# CLKB_clocking_system.net
KiCad netlist of a schematic drawn in Altium Designer
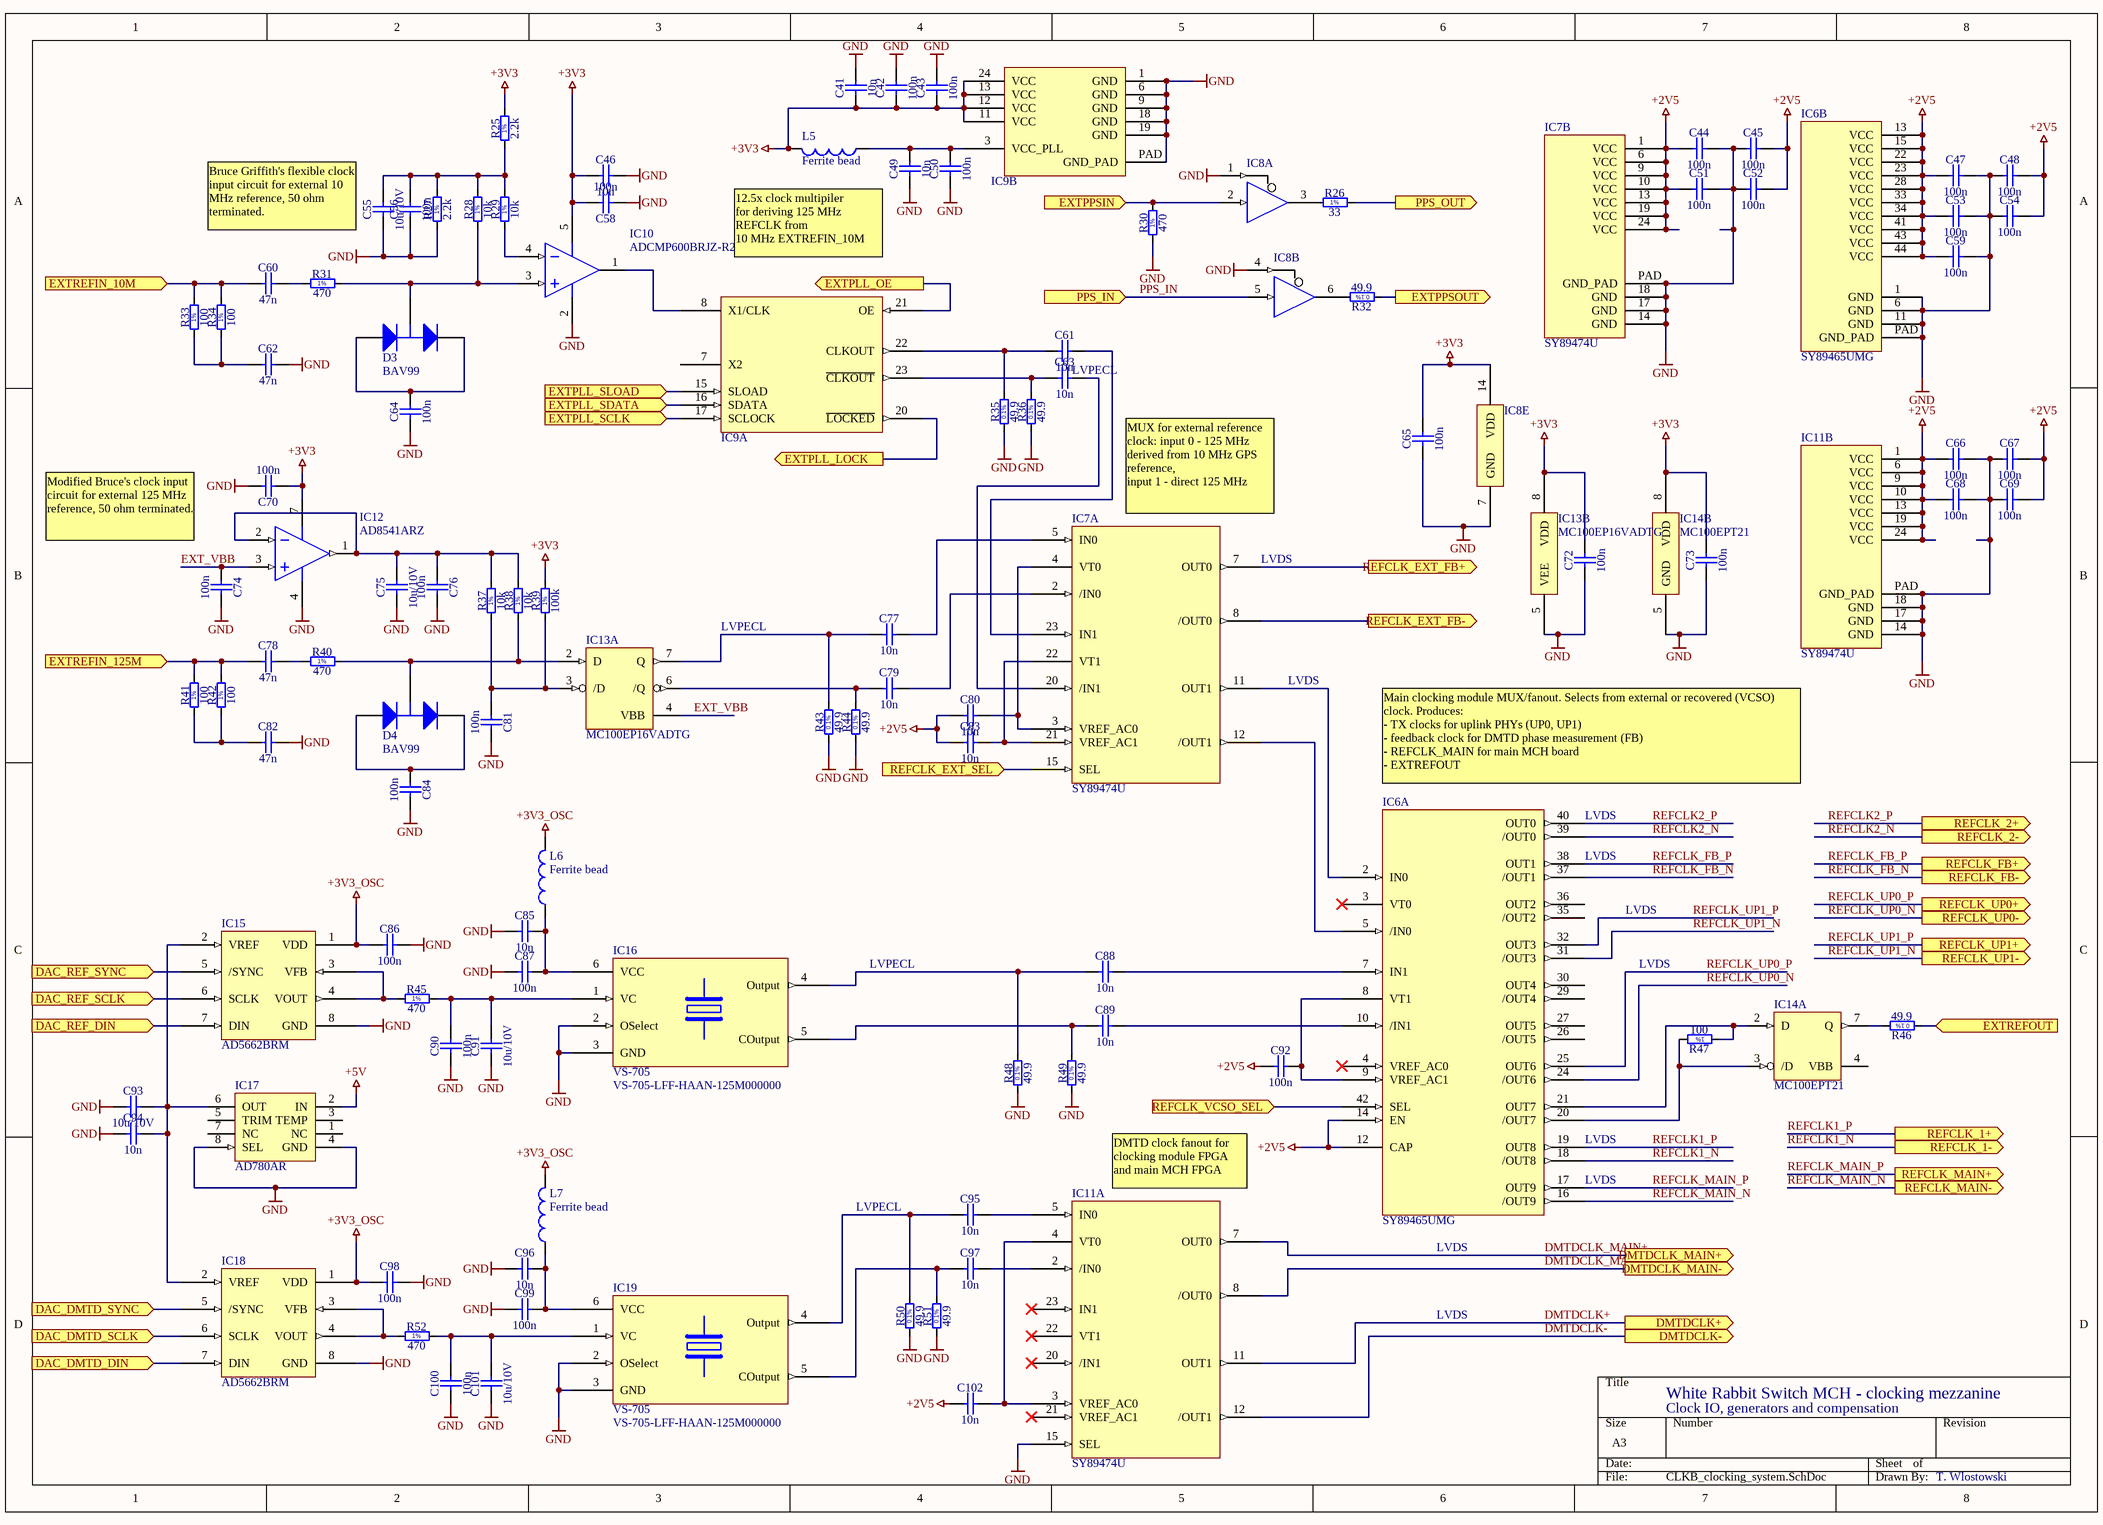
[diagram p0: CLKB_clocking_system.SchDoc]

(export (version "E")
  (design (tool "Eeschema 10.0.6"))
  (components
    (comp (ref "C41")
      (value "10n")
      (footprint "CAPC1608X87N")
      (description "Non-polarised capacitor")
      (fields
        (field (name "PART NUMBER") "CC0603_10NF_50V_10%_X7R")
        (field (name "VOLTAGE") "50V")
        (field (name "AUTHOR") "CERN DEM JLC")
      )
      (libsource (lib "Capacitors") (part "Capacitor - non polarized"))
    )
    (comp (ref "C42")
      (value "100n")
      (footprint "CAPC1608X87N")
      (description "Non-polarised capacitor")
      (fields
        (field (name "PART NUMBER") "CC0603_100NF_50V_10%_X7R")
        (field (name "VOLTAGE") "50V")
        (field (name "AUTHOR") "CERN DEM JLC")
      )
      (libsource (lib "Capacitors") (part "Capacitor - non polarized"))
    )
    (comp (ref "C43")
      (value "100n")
      (footprint "CAPC1608X87N")
      (description "Non-polarised capacitor")
      (fields
        (field (name "PART NUMBER") "CC0603_100NF_50V_10%_X7R")
        (field (name "VOLTAGE") "50V")
        (field (name "AUTHOR") "CERN DEM JLC")
      )
      (libsource (lib "Capacitors") (part "Capacitor - non polarized"))
    )
    (comp (ref "C44")
      (value "100n")
      (footprint "CAPC1608X87N")
      (description "Non-polarised capacitor")
      (fields
        (field (name "PART NUMBER") "CC0603_100NF_50V_10%_X7R")
        (field (name "VOLTAGE") "50V")
        (field (name "AUTHOR") "CERN DEM JLC")
      )
      (libsource (lib "Capacitors") (part "Capacitor - non polarized"))
    )
    (comp (ref "C45")
      (value "100n")
      (footprint "CAPC1608X87N")
      (description "Non-polarised capacitor")
      (fields
        (field (name "PART NUMBER") "CC0603_100NF_50V_10%_X7R")
        (field (name "VOLTAGE") "50V")
        (field (name "AUTHOR") "CERN DEM JLC")
      )
      (libsource (lib "Capacitors") (part "Capacitor - non polarized"))
    )
    (comp (ref "C46")
      (value "10n")
      (footprint "CAPC1608X87N")
      (description "Non-polarised capacitor")
      (fields
        (field (name "PART NUMBER") "CC0603_10NF_50V_10%_X7R")
        (field (name "VOLTAGE") "50V")
        (field (name "AUTHOR") "CERN DEM JLC")
      )
      (libsource (lib "Capacitors") (part "Capacitor - non polarized"))
    )
    (comp (ref "C47")
      (value "100n")
      (footprint "CAPC1608X87N")
      (description "Non-polarised capacitor")
      (fields
        (field (name "PART NUMBER") "CC0603_100NF_50V_10%_X7R")
        (field (name "VOLTAGE") "50V")
        (field (name "AUTHOR") "CERN DEM JLC")
      )
      (libsource (lib "Capacitors") (part "Capacitor - non polarized"))
    )
    (comp (ref "C48")
      (value "100n")
      (footprint "CAPC1608X87N")
      (description "Non-polarised capacitor")
      (fields
        (field (name "PART NUMBER") "CC0603_100NF_50V_10%_X7R")
        (field (name "VOLTAGE") "50V")
        (field (name "AUTHOR") "CERN DEM JLC")
      )
      (libsource (lib "Capacitors") (part "Capacitor - non polarized"))
    )
    (comp (ref "C49")
      (value "10n")
      (footprint "CAPC1608X87N")
      (description "Non-polarised capacitor")
      (fields
        (field (name "PART NUMBER") "CC0603_10NF_50V_10%_X7R")
        (field (name "VOLTAGE") "50V")
        (field (name "AUTHOR") "CERN DEM JLC")
      )
      (libsource (lib "Capacitors") (part "Capacitor - non polarized"))
    )
    (comp (ref "C50")
      (value "100n")
      (footprint "CAPC1608X87N")
      (description "Non-polarised capacitor")
      (fields
        (field (name "PART NUMBER") "CC0603_100NF_50V_10%_X7R")
        (field (name "VOLTAGE") "50V")
        (field (name "AUTHOR") "CERN DEM JLC")
      )
      (libsource (lib "Capacitors") (part "Capacitor - non polarized"))
    )
    (comp (ref "C51")
      (value "100n")
      (footprint "CAPC1608X87N")
      (description "Non-polarised capacitor")
      (fields
        (field (name "PART NUMBER") "CC0603_100NF_50V_10%_X7R")
        (field (name "VOLTAGE") "50V")
        (field (name "AUTHOR") "CERN DEM JLC")
      )
      (libsource (lib "Capacitors") (part "Capacitor - non polarized"))
    )
    (comp (ref "C52")
      (value "100n")
      (footprint "CAPC1608X87N")
      (description "Non-polarised capacitor")
      (fields
        (field (name "PART NUMBER") "CC0603_100NF_50V_10%_X7R")
        (field (name "VOLTAGE") "50V")
        (field (name "AUTHOR") "CERN DEM JLC")
      )
      (libsource (lib "Capacitors") (part "Capacitor - non polarized"))
    )
    (comp (ref "C53")
      (value "100n")
      (footprint "CAPC1608X87N")
      (description "Non-polarised capacitor")
      (fields
        (field (name "PART NUMBER") "CC0603_100NF_50V_10%_X7R")
        (field (name "VOLTAGE") "50V")
        (field (name "AUTHOR") "CERN DEM JLC")
      )
      (libsource (lib "Capacitors") (part "Capacitor - non polarized"))
    )
    (comp (ref "C54")
      (value "100n")
      (footprint "CAPC1608X87N")
      (description "Non-polarised capacitor")
      (fields
        (field (name "PART NUMBER") "CC0603_100NF_50V_10%_X7R")
        (field (name "VOLTAGE") "50V")
        (field (name "AUTHOR") "CERN DEM JLC")
      )
      (libsource (lib "Capacitors") (part "Capacitor - non polarized"))
    )
    (comp (ref "C55")
      (value "10u/10V")
      (footprint "CAPC3216X140N")
      (description "Non-polarised capacitor")
      (fields
        (field (name "PART NUMBER") "CC1206_10UF_10V_10%_X7R")
        (field (name "VOLTAGE") "10V")
        (field (name "AUTHOR") "CERN DEM JLC")
      )
      (libsource (lib "Capacitors") (part "Capacitor - non polarized"))
    )
    (comp (ref "C56")
      (value "100n")
      (footprint "CAPC1608X87N")
      (description "Non-polarised capacitor")
      (fields
        (field (name "PART NUMBER") "CC0603_100NF_50V_10%_X7R")
        (field (name "VOLTAGE") "50V")
        (field (name "AUTHOR") "CERN DEM JLC")
      )
      (libsource (lib "Capacitors") (part "Capacitor - non polarized"))
    )
    (comp (ref "C58")
      (value "100n")
      (footprint "CAPC1608X87N")
      (description "Non-polarised capacitor")
      (fields
        (field (name "PART NUMBER") "CC0603_100NF_50V_10%_X7R")
        (field (name "VOLTAGE") "50V")
        (field (name "AUTHOR") "CERN DEM JLC")
      )
      (libsource (lib "Capacitors") (part "Capacitor - non polarized"))
    )
    (comp (ref "C59")
      (value "100n")
      (footprint "CAPC1608X87N")
      (description "Non-polarised capacitor")
      (fields
        (field (name "PART NUMBER") "CC0603_100NF_50V_10%_X7R")
        (field (name "VOLTAGE") "50V")
        (field (name "AUTHOR") "CERN DEM JLC")
      )
      (libsource (lib "Capacitors") (part "Capacitor - non polarized"))
    )
    (comp (ref "C60")
      (value "47n")
      (footprint "CAPC1608X87N")
      (description "Non-polarised capacitor")
      (fields
        (field (name "PART NUMBER") "CC0603_47NF_25V_10%_X7R")
        (field (name "VOLTAGE") "25V")
        (field (name "AUTHOR") "CERN DEM JLC")
      )
      (libsource (lib "Capacitors") (part "Capacitor - non polarized"))
    )
    (comp (ref "C61")
      (value "10n")
      (footprint "CAPC1608X87N")
      (description "Non-polarised capacitor")
      (fields
        (field (name "PART NUMBER") "CC0603_10NF_50V_10%_X7R")
        (field (name "VOLTAGE") "50V")
        (field (name "AUTHOR") "CERN DEM JLC")
      )
      (libsource (lib "Capacitors") (part "Capacitor - non polarized"))
    )
    (comp (ref "C62")
      (value "47n")
      (footprint "CAPC1608X87N")
      (description "Non-polarised capacitor")
      (fields
        (field (name "PART NUMBER") "CC0603_47NF_25V_10%_X7R")
        (field (name "VOLTAGE") "25V")
        (field (name "AUTHOR") "CERN DEM JLC")
      )
      (libsource (lib "Capacitors") (part "Capacitor - non polarized"))
    )
    (comp (ref "C63")
      (value "10n")
      (footprint "CAPC1608X87N")
      (description "Non-polarised capacitor")
      (fields
        (field (name "PART NUMBER") "CC0603_10NF_50V_10%_X7R")
        (field (name "VOLTAGE") "50V")
        (field (name "AUTHOR") "CERN DEM JLC")
      )
      (libsource (lib "Capacitors") (part "Capacitor - non polarized"))
    )
    (comp (ref "C64")
      (value "100n")
      (footprint "CAPC1608X87N")
      (description "Non-polarised capacitor")
      (fields
        (field (name "PART NUMBER") "CC0603_100NF_50V_10%_X7R")
        (field (name "VOLTAGE") "50V")
        (field (name "AUTHOR") "CERN DEM JLC")
      )
      (libsource (lib "Capacitors") (part "Capacitor - non polarized"))
    )
    (comp (ref "C65")
      (value "100n")
      (footprint "CAPC1608X87N")
      (description "Non-polarised capacitor")
      (fields
        (field (name "PART NUMBER") "CC0603_100NF_50V_10%_X7R")
        (field (name "VOLTAGE") "50V")
        (field (name "AUTHOR") "CERN DEM JLC")
      )
      (libsource (lib "Capacitors") (part "Capacitor - non polarized"))
    )
    (comp (ref "C66")
      (value "100n")
      (footprint "CAPC1608X87N")
      (description "Non-polarised capacitor")
      (fields
        (field (name "PART NUMBER") "CC0603_100NF_50V_10%_X7R")
        (field (name "VOLTAGE") "50V")
        (field (name "AUTHOR") "CERN DEM JLC")
      )
      (libsource (lib "Capacitors") (part "Capacitor - non polarized"))
    )
    (comp (ref "C67")
      (value "100n")
      (footprint "CAPC1608X87N")
      (description "Non-polarised capacitor")
      (fields
        (field (name "PART NUMBER") "CC0603_100NF_50V_10%_X7R")
        (field (name "VOLTAGE") "50V")
        (field (name "AUTHOR") "CERN DEM JLC")
      )
      (libsource (lib "Capacitors") (part "Capacitor - non polarized"))
    )
    (comp (ref "C68")
      (value "100n")
      (footprint "CAPC1608X87N")
      (description "Non-polarised capacitor")
      (fields
        (field (name "PART NUMBER") "CC0603_100NF_50V_10%_X7R")
        (field (name "VOLTAGE") "50V")
        (field (name "AUTHOR") "CERN DEM JLC")
      )
      (libsource (lib "Capacitors") (part "Capacitor - non polarized"))
    )
    (comp (ref "C69")
      (value "100n")
      (footprint "CAPC1608X87N")
      (description "Non-polarised capacitor")
      (fields
        (field (name "PART NUMBER") "CC0603_100NF_50V_10%_X7R")
        (field (name "VOLTAGE") "50V")
        (field (name "AUTHOR") "CERN DEM JLC")
      )
      (libsource (lib "Capacitors") (part "Capacitor - non polarized"))
    )
    (comp (ref "C70")
      (value "100n")
      (footprint "CAPC1608X87N")
      (description "Non-polarised capacitor")
      (fields
        (field (name "PART NUMBER") "CC0603_100NF_50V_10%_X7R")
        (field (name "VOLTAGE") "50V")
        (field (name "AUTHOR") "CERN DEM JLC")
      )
      (libsource (lib "Capacitors") (part "Capacitor - non polarized"))
    )
    (comp (ref "C72")
      (value "100n")
      (footprint "CAPC1608X87N")
      (description "Non-polarised capacitor")
      (fields
        (field (name "PART NUMBER") "CC0603_100NF_50V_10%_X7R")
        (field (name "VOLTAGE") "50V")
        (field (name "AUTHOR") "CERN DEM JLC")
      )
      (libsource (lib "Capacitors") (part "Capacitor - non polarized"))
    )
    (comp (ref "C73")
      (value "100n")
      (footprint "CAPC1608X87N")
      (description "Non-polarised capacitor")
      (fields
        (field (name "PART NUMBER") "CC0603_100NF_50V_10%_X7R")
        (field (name "VOLTAGE") "50V")
        (field (name "AUTHOR") "CERN DEM JLC")
      )
      (libsource (lib "Capacitors") (part "Capacitor - non polarized"))
    )
    (comp (ref "C74")
      (value "100n")
      (footprint "CAPC1608X87N")
      (description "Non-polarised capacitor")
      (fields
        (field (name "PART NUMBER") "CC0603_100NF_50V_10%_X7R")
        (field (name "VOLTAGE") "50V")
        (field (name "AUTHOR") "CERN DEM JLC")
      )
      (libsource (lib "Capacitors") (part "Capacitor - non polarized"))
    )
    (comp (ref "C75")
      (value "10u/10V")
      (footprint "CAPC3216X140N")
      (description "Non-polarised capacitor")
      (fields
        (field (name "PART NUMBER") "CC1206_10UF_10V_10%_X7R")
        (field (name "VOLTAGE") "10V")
        (field (name "AUTHOR") "CERN DEM JLC")
      )
      (libsource (lib "Capacitors") (part "Capacitor - non polarized"))
    )
    (comp (ref "C76")
      (value "100n")
      (footprint "CAPC1608X87N")
      (description "Non-polarised capacitor")
      (fields
        (field (name "PART NUMBER") "CC0603_100NF_50V_10%_X7R")
        (field (name "VOLTAGE") "50V")
        (field (name "AUTHOR") "CERN DEM JLC")
      )
      (libsource (lib "Capacitors") (part "Capacitor - non polarized"))
    )
    (comp (ref "C77")
      (value "10n")
      (footprint "CAPC1608X87N")
      (description "Non-polarised capacitor")
      (fields
        (field (name "PART NUMBER") "CC0603_10NF_50V_10%_X7R")
        (field (name "VOLTAGE") "50V")
        (field (name "AUTHOR") "CERN DEM JLC")
      )
      (libsource (lib "Capacitors") (part "Capacitor - non polarized"))
    )
    (comp (ref "C78")
      (value "47n")
      (footprint "CAPC1608X87N")
      (description "Non-polarised capacitor")
      (fields
        (field (name "PART NUMBER") "CC0603_47NF_25V_10%_X7R")
        (field (name "VOLTAGE") "25V")
        (field (name "AUTHOR") "CERN DEM JLC")
      )
      (libsource (lib "Capacitors") (part "Capacitor - non polarized"))
    )
    (comp (ref "C79")
      (value "10n")
      (footprint "CAPC1608X87N")
      (description "Non-polarised capacitor")
      (fields
        (field (name "PART NUMBER") "CC0603_10NF_50V_10%_X7R")
        (field (name "VOLTAGE") "50V")
        (field (name "AUTHOR") "CERN DEM JLC")
      )
      (libsource (lib "Capacitors") (part "Capacitor - non polarized"))
    )
    (comp (ref "C80")
      (value "10n")
      (footprint "CAPC1608X87N")
      (description "Non-polarised capacitor")
      (fields
        (field (name "PART NUMBER") "CC0603_10NF_50V_10%_X7R")
        (field (name "VOLTAGE") "50V")
        (field (name "AUTHOR") "CERN DEM JLC")
      )
      (libsource (lib "Capacitors") (part "Capacitor - non polarized"))
    )
    (comp (ref "C81")
      (value "100n")
      (footprint "CAPC1608X87N")
      (description "Non-polarised capacitor")
      (fields
        (field (name "PART NUMBER") "CC0603_100NF_50V_10%_X7R")
        (field (name "VOLTAGE") "50V")
        (field (name "AUTHOR") "CERN DEM JLC")
      )
      (libsource (lib "Capacitors") (part "Capacitor - non polarized"))
    )
    (comp (ref "C82")
      (value "47n")
      (footprint "CAPC1608X87N")
      (description "Non-polarised capacitor")
      (fields
        (field (name "PART NUMBER") "CC0603_47NF_25V_10%_X7R")
        (field (name "VOLTAGE") "25V")
        (field (name "AUTHOR") "CERN DEM JLC")
      )
      (libsource (lib "Capacitors") (part "Capacitor - non polarized"))
    )
    (comp (ref "C83")
      (value "10n")
      (footprint "CAPC1608X87N")
      (description "Non-polarised capacitor")
      (fields
        (field (name "PART NUMBER") "CC0603_10NF_50V_10%_X7R")
        (field (name "VOLTAGE") "50V")
        (field (name "AUTHOR") "CERN DEM JLC")
      )
      (libsource (lib "Capacitors") (part "Capacitor - non polarized"))
    )
    (comp (ref "C84")
      (value "100n")
      (footprint "CAPC1608X87N")
      (description "Non-polarised capacitor")
      (fields
        (field (name "PART NUMBER") "CC0603_100NF_50V_10%_X7R")
        (field (name "VOLTAGE") "50V")
        (field (name "AUTHOR") "CERN DEM JLC")
      )
      (libsource (lib "Capacitors") (part "Capacitor - non polarized"))
    )
    (comp (ref "C85")
      (value "10n")
      (footprint "CAPC1608X87N")
      (description "Non-polarised capacitor")
      (fields
        (field (name "PART NUMBER") "CC0603_10NF_50V_10%_X7R")
        (field (name "VOLTAGE") "50V")
        (field (name "AUTHOR") "CERN DEM JLC")
      )
      (libsource (lib "Capacitors") (part "Capacitor - non polarized"))
    )
    (comp (ref "C86")
      (value "100n")
      (footprint "CAPC1608X87N")
      (description "Non-polarised capacitor")
      (fields
        (field (name "PART NUMBER") "CC0603_100NF_50V_10%_X7R")
        (field (name "VOLTAGE") "50V")
        (field (name "AUTHOR") "CERN DEM JLC")
      )
      (libsource (lib "Capacitors") (part "Capacitor - non polarized"))
    )
    (comp (ref "C87")
      (value "100n")
      (footprint "CAPC1608X87N")
      (description "Non-polarised capacitor")
      (fields
        (field (name "PART NUMBER") "CC0603_100NF_50V_10%_X7R")
        (field (name "VOLTAGE") "50V")
        (field (name "AUTHOR") "CERN DEM JLC")
      )
      (libsource (lib "Capacitors") (part "Capacitor - non polarized"))
    )
    (comp (ref "C88")
      (value "10n")
      (footprint "CAPC1608X87N")
      (description "Non-polarised capacitor")
      (fields
        (field (name "PART NUMBER") "CC0603_10NF_50V_10%_X7R")
        (field (name "VOLTAGE") "50V")
        (field (name "AUTHOR") "CERN DEM JLC")
      )
      (libsource (lib "Capacitors") (part "Capacitor - non polarized"))
    )
    (comp (ref "C89")
      (value "10n")
      (footprint "CAPC1608X87N")
      (description "Non-polarised capacitor")
      (fields
        (field (name "PART NUMBER") "CC0603_10NF_50V_10%_X7R")
        (field (name "VOLTAGE") "50V")
        (field (name "AUTHOR") "CERN DEM JLC")
      )
      (libsource (lib "Capacitors") (part "Capacitor - non polarized"))
    )
    (comp (ref "C90")
      (value "100n")
      (footprint "CAPC1608X87N")
      (description "Non-polarised capacitor")
      (fields
        (field (name "PART NUMBER") "CC0603_100NF_50V_10%_X7R")
        (field (name "VOLTAGE") "50V")
        (field (name "AUTHOR") "CERN DEM JLC")
      )
      (libsource (lib "Capacitors") (part "Capacitor - non polarized"))
    )
    (comp (ref "C91")
      (value "10u/10V")
      (footprint "CAPC3216X140N")
      (description "Non-polarised capacitor")
      (fields
        (field (name "PART NUMBER") "CC1206_10UF_10V_10%_X7R")
        (field (name "VOLTAGE") "10V")
        (field (name "AUTHOR") "CERN DEM JLC")
      )
      (libsource (lib "Capacitors") (part "Capacitor - non polarized"))
    )
    (comp (ref "C92")
      (value "100n")
      (footprint "CAPC1608X87N")
      (description "Non-polarised capacitor")
      (fields
        (field (name "PART NUMBER") "CC0603_100NF_50V_10%_X7R")
        (field (name "VOLTAGE") "50V")
        (field (name "AUTHOR") "CERN DEM JLC")
      )
      (libsource (lib "Capacitors") (part "Capacitor - non polarized"))
    )
    (comp (ref "C93")
      (value "10u/10V")
      (footprint "CAPC3216X140N")
      (description "Non-polarised capacitor")
      (fields
        (field (name "PART NUMBER") "CC1206_10UF_10V_10%_X7R")
        (field (name "VOLTAGE") "10V")
        (field (name "AUTHOR") "CERN DEM JLC")
      )
      (libsource (lib "Capacitors") (part "Capacitor - non polarized"))
    )
    (comp (ref "C94")
      (value "10n")
      (footprint "CAPC1608X87N")
      (description "Non-polarised capacitor")
      (fields
        (field (name "PART NUMBER") "CC0603_10NF_50V_10%_X7R")
        (field (name "VOLTAGE") "50V")
        (field (name "AUTHOR") "CERN DEM JLC")
      )
      (libsource (lib "Capacitors") (part "Capacitor - non polarized"))
    )
    (comp (ref "C95")
      (value "10n")
      (footprint "CAPC1608X87N")
      (description "Non-polarised capacitor")
      (fields
        (field (name "PART NUMBER") "CC0603_10NF_50V_10%_X7R")
        (field (name "VOLTAGE") "50V")
        (field (name "AUTHOR") "CERN DEM JLC")
      )
      (libsource (lib "Capacitors") (part "Capacitor - non polarized"))
    )
    (comp (ref "C96")
      (value "10n")
      (footprint "CAPC1608X87N")
      (description "Non-polarised capacitor")
      (fields
        (field (name "PART NUMBER") "CC0603_10NF_50V_10%_X7R")
        (field (name "VOLTAGE") "50V")
        (field (name "AUTHOR") "CERN DEM JLC")
      )
      (libsource (lib "Capacitors") (part "Capacitor - non polarized"))
    )
    (comp (ref "C97")
      (value "10n")
      (footprint "CAPC1608X87N")
      (description "Non-polarised capacitor")
      (fields
        (field (name "PART NUMBER") "CC0603_10NF_50V_10%_X7R")
        (field (name "VOLTAGE") "50V")
        (field (name "AUTHOR") "CERN DEM JLC")
      )
      (libsource (lib "Capacitors") (part "Capacitor - non polarized"))
    )
    (comp (ref "C98")
      (value "100n")
      (footprint "CAPC1608X87N")
      (description "Non-polarised capacitor")
      (fields
        (field (name "PART NUMBER") "CC0603_100NF_50V_10%_X7R")
        (field (name "VOLTAGE") "50V")
        (field (name "AUTHOR") "CERN DEM JLC")
      )
      (libsource (lib "Capacitors") (part "Capacitor - non polarized"))
    )
    (comp (ref "C99")
      (value "100n")
      (footprint "CAPC1608X87N")
      (description "Non-polarised capacitor")
      (fields
        (field (name "PART NUMBER") "CC0603_100NF_50V_10%_X7R")
        (field (name "VOLTAGE") "50V")
        (field (name "AUTHOR") "CERN DEM JLC")
      )
      (libsource (lib "Capacitors") (part "Capacitor - non polarized"))
    )
    (comp (ref "C100")
      (value "100n")
      (footprint "CAPC1608X87N")
      (description "Non-polarised capacitor")
      (fields
        (field (name "PART NUMBER") "CC0603_100NF_50V_10%_X7R")
        (field (name "VOLTAGE") "50V")
        (field (name "AUTHOR") "CERN DEM JLC")
      )
      (libsource (lib "Capacitors") (part "Capacitor - non polarized"))
    )
    (comp (ref "C101")
      (value "10u/10V")
      (footprint "CAPC3216X140N")
      (description "Non-polarised capacitor")
      (fields
        (field (name "PART NUMBER") "CC1206_10UF_10V_10%_X7R")
        (field (name "VOLTAGE") "10V")
        (field (name "AUTHOR") "CERN DEM JLC")
      )
      (libsource (lib "Capacitors") (part "Capacitor - non polarized"))
    )
    (comp (ref "C102")
      (value "10n")
      (footprint "CAPC1608X87N")
      (description "Non-polarised capacitor")
      (fields
        (field (name "PART NUMBER") "CC0603_10NF_50V_10%_X7R")
        (field (name "VOLTAGE") "50V")
        (field (name "AUTHOR") "CERN DEM JLC")
      )
      (libsource (lib "Capacitors") (part "Capacitor - non polarized"))
    )
    (comp (ref "D3")
      (value "BAV99")
      (footprint "SOT-23")
      (description "Silicon Switching Diode Array for High-Speed Switching")
      (fields (field (name "PUBLISHER") "Altium Limited"))
      (libsource (lib "Infineon Discrete Diode") (part "BAV99"))
    )
    (comp (ref "D4")
      (value "BAV99")
      (footprint "SOT-23")
      (description "Silicon Switching Diode Array for High-Speed Switching")
      (fields (field (name "PUBLISHER") "Altium Limited"))
      (libsource (lib "Infineon Discrete Diode") (part "BAV99"))
    )
    (comp (ref "IC6")
      (value "SY89465UMG")
      (footprint "MLF44")
      (description "Micrel 2:10 any->LVDS clock fanout")
      (fields (field (name "Comment") "SY89465U"))
      (libsource (lib "wr_switch") (part "SY89465U"))
    )
    (comp (ref "IC7")
      (value "SY89474U")
      (footprint "MLF24")
      (description "2:1 differential clock mux/2-output fanout")
      (libsource (lib "wr_switch") (part "SY89474U"))
    )
    (comp (ref "IC8")
      (value "SN74ALVC125")
      (footprint "SO-14")
      (description "Quad Buffer with 3-State Outputs with TTL Compatible Inputs")
      (libsource (lib "wr_switch") (part "SN74ALVC125"))
    )
    (comp (ref "IC9")
      (value "NB4n441")
      (footprint "QFN50P400X400-24W4M")
      (description "OnSemi single-chip clock synthesizer")
      (libsource (lib "wr_switch") (part "NB4n441"))
    )
    (comp (ref "IC10")
      (value "ADCMP600BRJZ-R2")
      (footprint "SOT23-5AL")
      (description "Analog Devices fast comparator")
      (fields (field (name "Comment") "ADCMP600"))
      (libsource (lib "wr_switch") (part "ADCMP600"))
    )
    (comp (ref "IC11")
      (value "SY89474U")
      (footprint "MLF24")
      (description "2:1 differential clock mux/2-output fanout")
      (libsource (lib "wr_switch") (part "SY89474U"))
    )
    (comp (ref "IC12")
      (value "AD8541ARZ")
      (footprint "SOIC127P600-8AL")
      (description "Analog Devices general purpose low-voltage R2R CMOS opamp")
      (fields (field (name "Comment") "AD8541"))
      (libsource (lib "wr_switch") (part "AD8541"))
    )
    (comp (ref "IC13")
      (value "MC100EP16VADTG")
      (footprint "TSOP65P490-8AN")
      (description "ONSemi differental receiver w/ECL output")
      (fields (field (name "Comment") "MC100EP16"))
      (libsource (lib "wr_switch") (part "MC100EP16"))
    )
    (comp (ref "IC14")
      (value "MC100EPT21")
      (footprint "TSOP65P490-8AN")
      (description "ONSemi LVDS/LVPECL -> LVTTL/LVCMOS buffer")
      (libsource (lib "wr_switch") (part "MC100EPT21"))
    )
    (comp (ref "IC15")
      (value "AD5662BRM")
      (footprint "TSOP65P490-8AN")
      (description "Analog Devices 16-bit DAC w/SPI interface, ext ref")
      (fields (field (name "Comment") "AD5662B"))
      (libsource (lib "wr_switch") (part "AD5662"))
    )
    (comp (ref "IC16")
      (value "VS-705")
      (footprint "VS-705")
      (description "Vectron Voltage Controlled SAW Oscillator")
      (fields (field (name "ALTIUM_VALUE") "VS-705-LFF-HAAN-125M000000"))
      (libsource (lib "wr_switch") (part "VS-705"))
    )
    (comp (ref "IC17")
      (value "AD780AR")
      (footprint "R-8C_M")
      (description "2.5V/3.0V High-Precision Reference")
      (fields (field (name "PUBLISHER") "Altium Limited"))
      (libsource (lib "AD Power Mgt Voltage Reference") (part "AD780AR"))
    )
    (comp (ref "IC18")
      (value "AD5662BRM")
      (footprint "TSOP65P490-8AN")
      (description "Analog Devices 16-bit DAC w/SPI interface, ext ref")
      (fields (field (name "Comment") "AD5662B"))
      (libsource (lib "wr_switch") (part "AD5662"))
    )
    (comp (ref "IC19")
      (value "VS-705")
      (footprint "VS-705")
      (description "Vectron Voltage Controlled SAW Oscillator")
      (fields (field (name "ALTIUM_VALUE") "VS-705-LFF-HAAN-125M000000"))
      (libsource (lib "wr_switch") (part "VS-705"))
    )
    (comp (ref "L5")
      (value "Ferrite bead")
      (footprint "INDC2012-0805")
      (fields (field (name "PUBLISHER") "Altium Limited"))
      (libsource (lib "Miscellaneous Devices") (part "Inductor"))
    )
    (comp (ref "L6")
      (value "Ferrite bead")
      (footprint "INDC2012-0805")
      (fields (field (name "PUBLISHER") "Altium Limited"))
      (libsource (lib "Miscellaneous Devices") (part "Inductor"))
    )
    (comp (ref "L7")
      (value "Ferrite bead")
      (footprint "INDC2012-0805")
      (fields (field (name "PUBLISHER") "Altium Limited"))
      (libsource (lib "Miscellaneous Devices") (part "Inductor"))
    )
    (comp (ref "R25")
      (value "2.2k")
      (footprint "RESC1608X55N")
      (description "Resistor - 1%")
      (fields
        (field (name "PART NUMBER") "R0603_2K2_1%_0.1W_100PPM")
        (field (name "POWER") "0.1W")
        (field (name "AUTHOR") "CERN DEM JLC")
      )
      (libsource (lib "Resistors") (part "Resistor - 1%"))
    )
    (comp (ref "R26")
      (value "33")
      (footprint "RESC1608X55N")
      (description "Resistor - 1%")
      (fields
        (field (name "PART NUMBER") "R0603_33R_1%_0.1W_100PPM")
        (field (name "POWER") "0.1W")
        (field (name "AUTHOR") "CERN DEM JLC")
      )
      (libsource (lib "Resistors") (part "Resistor - 1%"))
    )
    (comp (ref "R27")
      (value "2.2k")
      (footprint "RESC1608X55N")
      (description "Resistor - 1%")
      (fields
        (field (name "PART NUMBER") "R0603_2K2_1%_0.1W_100PPM")
        (field (name "POWER") "0.1W")
        (field (name "AUTHOR") "CERN DEM JLC")
      )
      (libsource (lib "Resistors") (part "Resistor - 1%"))
    )
    (comp (ref "R28")
      (value "10k")
      (footprint "RESC1608X55N")
      (description "Resistor - 1%")
      (fields
        (field (name "PART NUMBER") "R0603_10K_1%_0.1W_100PPM")
        (field (name "POWER") "0.1W")
        (field (name "AUTHOR") "CERN DEM JLC")
      )
      (libsource (lib "Resistors") (part "Resistor - 1%"))
    )
    (comp (ref "R29")
      (value "10k")
      (footprint "RESC1608X55N")
      (description "Resistor - 1%")
      (fields
        (field (name "PART NUMBER") "R0603_10K_1%_0.1W_100PPM")
        (field (name "POWER") "0.1W")
        (field (name "AUTHOR") "CERN DEM JLC")
      )
      (libsource (lib "Resistors") (part "Resistor - 1%"))
    )
    (comp (ref "R30")
      (value "470")
      (footprint "RESC1608X55N")
      (description "Resistor - 1%")
      (fields
        (field (name "PART NUMBER") "R0603_470R_1%_0.1W_100PPM")
        (field (name "POWER") "0.1W")
        (field (name "AUTHOR") "CERN DEM JLC")
      )
      (libsource (lib "Resistors") (part "Resistor - 1%"))
    )
    (comp (ref "R31")
      (value "470")
      (footprint "RESC1608X55N")
      (description "Resistor - 1%")
      (fields
        (field (name "PART NUMBER") "R0603_470R_1%_0.1W_100PPM")
        (field (name "POWER") "0.1W")
        (field (name "AUTHOR") "CERN DEM JLC")
      )
      (libsource (lib "Resistors") (part "Resistor - 1%"))
    )
    (comp (ref "R32")
      (value "49.9")
      (footprint "RESC1608X55N")
      (description "Resistor - 0.1%")
      (fields
        (field (name "PART NUMBER") "R0603_49R9_0.1%_0.063W_10PPM")
        (field (name "POWER") "0.063W")
        (field (name "AUTHOR") "CERN DEM JLC")
      )
      (libsource (lib "Resistors") (part "Resistor - 0.1%"))
    )
    (comp (ref "R33")
      (value "100")
      (footprint "RESC1608X55N")
      (description "Resistor - 1%")
      (fields
        (field (name "PART NUMBER") "R0603_100R_1%_0.1W_100PPM")
        (field (name "POWER") "0.1W")
        (field (name "AUTHOR") "CERN DEM JLC")
      )
      (libsource (lib "Resistors") (part "Resistor - 1%"))
    )
    (comp (ref "R34")
      (value "100")
      (footprint "RESC1608X55N")
      (description "Resistor - 1%")
      (fields
        (field (name "PART NUMBER") "R0603_100R_1%_0.1W_100PPM")
        (field (name "POWER") "0.1W")
        (field (name "AUTHOR") "CERN DEM JLC")
      )
      (libsource (lib "Resistors") (part "Resistor - 1%"))
    )
    (comp (ref "R35")
      (value "49.9")
      (footprint "RESC1608X55N")
      (description "Resistor - 0.1%")
      (fields
        (field (name "PART NUMBER") "R0603_49R9_0.1%_0.063W_10PPM")
        (field (name "POWER") "0.063W")
        (field (name "AUTHOR") "CERN DEM JLC")
      )
      (libsource (lib "Resistors") (part "Resistor - 0.1%"))
    )
    (comp (ref "R36")
      (value "49.9")
      (footprint "RESC1608X55N")
      (description "Resistor - 0.1%")
      (fields
        (field (name "PART NUMBER") "R0603_49R9_0.1%_0.063W_10PPM")
        (field (name "POWER") "0.063W")
        (field (name "AUTHOR") "CERN DEM JLC")
      )
      (libsource (lib "Resistors") (part "Resistor - 0.1%"))
    )
    (comp (ref "R37")
      (value "10k")
      (footprint "RESC1608X55N")
      (description "Resistor - 1%")
      (fields
        (field (name "PART NUMBER") "R0603_10K_1%_0.1W_100PPM")
        (field (name "POWER") "0.1W")
        (field (name "AUTHOR") "CERN DEM JLC")
      )
      (libsource (lib "Resistors") (part "Resistor - 1%"))
    )
    (comp (ref "R38")
      (value "10k")
      (footprint "RESC1608X55N")
      (description "Resistor - 1%")
      (fields
        (field (name "PART NUMBER") "R0603_10K_1%_0.1W_100PPM")
        (field (name "POWER") "0.1W")
        (field (name "AUTHOR") "CERN DEM JLC")
      )
      (libsource (lib "Resistors") (part "Resistor - 1%"))
    )
    (comp (ref "R39")
      (value "100k")
      (footprint "RESC1608X55N")
      (description "Resistor - 1%")
      (fields
        (field (name "PART NUMBER") "R0603_100K_1%_0.1W_100PPM")
        (field (name "POWER") "0.1W")
        (field (name "AUTHOR") "CERN DEM JLC")
      )
      (libsource (lib "Resistors") (part "Resistor - 1%"))
    )
    (comp (ref "R40")
      (value "470")
      (footprint "RESC1608X55N")
      (description "Resistor - 1%")
      (fields
        (field (name "PART NUMBER") "R0603_470R_1%_0.1W_100PPM")
        (field (name "POWER") "0.1W")
        (field (name "AUTHOR") "CERN DEM JLC")
      )
      (libsource (lib "Resistors") (part "Resistor - 1%"))
    )
    (comp (ref "R41")
      (value "100")
      (footprint "RESC1608X55N")
      (description "Resistor - 1%")
      (fields
        (field (name "PART NUMBER") "R0603_100R_1%_0.1W_100PPM")
        (field (name "POWER") "0.1W")
        (field (name "AUTHOR") "CERN DEM JLC")
      )
      (libsource (lib "Resistors") (part "Resistor - 1%"))
    )
    (comp (ref "R42")
      (value "100")
      (footprint "RESC1608X55N")
      (description "Resistor - 1%")
      (fields
        (field (name "PART NUMBER") "R0603_100R_1%_0.1W_100PPM")
        (field (name "POWER") "0.1W")
        (field (name "AUTHOR") "CERN DEM JLC")
      )
      (libsource (lib "Resistors") (part "Resistor - 1%"))
    )
    (comp (ref "R43")
      (value "49.9")
      (footprint "RESC1608X55N")
      (description "Resistor - 0.1%")
      (fields
        (field (name "PART NUMBER") "R0603_49R9_0.1%_0.063W_10PPM")
        (field (name "POWER") "0.063W")
        (field (name "AUTHOR") "CERN DEM JLC")
      )
      (libsource (lib "Resistors") (part "Resistor - 0.1%"))
    )
    (comp (ref "R44")
      (value "49.9")
      (footprint "RESC1608X55N")
      (description "Resistor - 0.1%")
      (fields
        (field (name "PART NUMBER") "R0603_49R9_0.1%_0.063W_10PPM")
        (field (name "POWER") "0.063W")
        (field (name "AUTHOR") "CERN DEM JLC")
      )
      (libsource (lib "Resistors") (part "Resistor - 0.1%"))
    )
    (comp (ref "R45")
      (value "470")
      (footprint "RESC1608X55N")
      (description "Resistor - 1%")
      (fields
        (field (name "PART NUMBER") "R0603_470R_1%_0.1W_100PPM")
        (field (name "POWER") "0.1W")
        (field (name "AUTHOR") "CERN DEM JLC")
      )
      (libsource (lib "Resistors") (part "Resistor - 1%"))
    )
    (comp (ref "R46")
      (value "49.9")
      (footprint "RESC1608X55N")
      (description "Resistor - 0.1%")
      (fields
        (field (name "PART NUMBER") "R0603_49R9_0.1%_0.063W_10PPM")
        (field (name "POWER") "0.063W")
        (field (name "AUTHOR") "CERN DEM JLC")
      )
      (libsource (lib "Resistors") (part "Resistor - 0.1%"))
    )
    (comp (ref "R47")
      (value "100")
      (footprint "RESC1608X55N")
      (description "Resistor - 1%")
      (fields
        (field (name "PART NUMBER") "R0603_100R_1%_0.1W_100PPM")
        (field (name "POWER") "0.1W")
        (field (name "AUTHOR") "CERN DEM JLC")
      )
      (libsource (lib "Resistors") (part "Resistor - 1%"))
    )
    (comp (ref "R48")
      (value "49.9")
      (footprint "RESC1608X55N")
      (description "Resistor - 0.1%")
      (fields
        (field (name "PART NUMBER") "R0603_49R9_0.1%_0.063W_10PPM")
        (field (name "POWER") "0.063W")
        (field (name "AUTHOR") "CERN DEM JLC")
      )
      (libsource (lib "Resistors") (part "Resistor - 0.1%"))
    )
    (comp (ref "R49")
      (value "49.9")
      (footprint "RESC1608X55N")
      (description "Resistor - 0.1%")
      (fields
        (field (name "PART NUMBER") "R0603_49R9_0.1%_0.063W_10PPM")
        (field (name "POWER") "0.063W")
        (field (name "AUTHOR") "CERN DEM JLC")
      )
      (libsource (lib "Resistors") (part "Resistor - 0.1%"))
    )
    (comp (ref "R50")
      (value "49.9")
      (footprint "RESC1608X55N")
      (description "Resistor - 0.1%")
      (fields
        (field (name "PART NUMBER") "R0603_49R9_0.1%_0.063W_10PPM")
        (field (name "POWER") "0.063W")
        (field (name "AUTHOR") "CERN DEM JLC")
      )
      (libsource (lib "Resistors") (part "Resistor - 0.1%"))
    )
    (comp (ref "R51")
      (value "49.9")
      (footprint "RESC1608X55N")
      (description "Resistor - 0.1%")
      (fields
        (field (name "PART NUMBER") "R0603_49R9_0.1%_0.063W_10PPM")
        (field (name "POWER") "0.063W")
        (field (name "AUTHOR") "CERN DEM JLC")
      )
      (libsource (lib "Resistors") (part "Resistor - 0.1%"))
    )
    (comp (ref "R52")
      (value "470")
      (footprint "RESC1608X55N")
      (description "Resistor - 1%")
      (fields
        (field (name "PART NUMBER") "R0603_470R_1%_0.1W_100PPM")
        (field (name "POWER") "0.1W")
        (field (name "AUTHOR") "CERN DEM JLC")
      )
      (libsource (lib "Resistors") (part "Resistor - 1%"))
    )
  )
  (nets
    (net (code "1") (name "+2V5") (class "Default")
      (node (ref "C102") (pin "1") (pinfunction "1_1") (pintype "passive"))
      (node (ref "C44") (pin "1") (pinfunction "1_1") (pintype "passive"))
      (node (ref "C45") (pin "2") (pinfunction "2_2") (pintype "passive"))
      (node (ref "C47") (pin "1") (pinfunction "1_1") (pintype "passive"))
      (node (ref "C48") (pin "2") (pinfunction "2_2") (pintype "passive"))
      (node (ref "C51") (pin "1") (pinfunction "1_1") (pintype "passive"))
      (node (ref "C52") (pin "2") (pinfunction "2_2") (pintype "passive"))
      (node (ref "C53") (pin "1") (pinfunction "1_1") (pintype "passive"))
      (node (ref "C54") (pin "2") (pinfunction "2_2") (pintype "passive"))
      (node (ref "C59") (pin "1") (pinfunction "1_1") (pintype "passive"))
      (node (ref "C66") (pin "1") (pinfunction "1_1") (pintype "passive"))
      (node (ref "C67") (pin "2") (pinfunction "2_2") (pintype "passive"))
      (node (ref "C68") (pin "1") (pinfunction "1_1") (pintype "passive"))
      (node (ref "C69") (pin "2") (pinfunction "2_2") (pintype "passive"))
      (node (ref "C80") (pin "1") (pinfunction "1_1") (pintype "passive"))
      (node (ref "C83") (pin "1") (pinfunction "1_1") (pintype "passive"))
      (node (ref "C92") (pin "1") (pinfunction "1_1") (pintype "passive"))
      (node (ref "IC11") (pin "1") (pinfunction "VCC_1") (pintype "power_in"))
      (node (ref "IC11") (pin "10") (pinfunction "VCC_10") (pintype "power_in"))
      (node (ref "IC11") (pin "13") (pinfunction "VCC_13") (pintype "power_in"))
      (node (ref "IC11") (pin "19") (pinfunction "VCC_19") (pintype "power_in"))
      (node (ref "IC11") (pin "24") (pinfunction "VCC_24") (pintype "power_in"))
      (node (ref "IC11") (pin "6") (pinfunction "VCC_6") (pintype "power_in"))
      (node (ref "IC11") (pin "9") (pinfunction "VCC_9") (pintype "power_in"))
      (node (ref "IC6") (pin "12") (pinfunction "CAP_12") (pintype "passive"))
      (node (ref "IC6") (pin "13") (pinfunction "VCC_13") (pintype "power_in"))
      (node (ref "IC6") (pin "14") (pinfunction "EN_14") (pintype "input"))
      (node (ref "IC6") (pin "15") (pinfunction "VCC_15") (pintype "power_in"))
      (node (ref "IC6") (pin "22") (pinfunction "VCC_22") (pintype "power_in"))
      (node (ref "IC6") (pin "23") (pinfunction "VCC_23") (pintype "power_in"))
      (node (ref "IC6") (pin "28") (pinfunction "VCC_28") (pintype "power_in"))
      (node (ref "IC6") (pin "33") (pinfunction "VCC_33") (pintype "power_in"))
      (node (ref "IC6") (pin "34") (pinfunction "VCC_34") (pintype "power_in"))
      (node (ref "IC6") (pin "41") (pinfunction "VCC_41") (pintype "power_in"))
      (node (ref "IC6") (pin "43") (pinfunction "VCC_43") (pintype "power_in"))
      (node (ref "IC6") (pin "44") (pinfunction "VCC_44") (pintype "power_in"))
      (node (ref "IC7") (pin "1") (pinfunction "VCC_1") (pintype "power_in"))
      (node (ref "IC7") (pin "10") (pinfunction "VCC_10") (pintype "power_in"))
      (node (ref "IC7") (pin "13") (pinfunction "VCC_13") (pintype "power_in"))
      (node (ref "IC7") (pin "19") (pinfunction "VCC_19") (pintype "power_in"))
      (node (ref "IC7") (pin "24") (pinfunction "VCC_24") (pintype "power_in"))
      (node (ref "IC7") (pin "6") (pinfunction "VCC_6") (pintype "power_in"))
      (node (ref "IC7") (pin "9") (pinfunction "VCC_9") (pintype "power_in"))
    )
    (net (code "2") (name "+3V3") (class "Default")
      (node (ref "C41") (pin "1") (pinfunction "1_1") (pintype "passive"))
      (node (ref "C42") (pin "1") (pinfunction "1_1") (pintype "passive"))
      (node (ref "C43") (pin "1") (pinfunction "1_1") (pintype "passive"))
      (node (ref "C46") (pin "1") (pinfunction "1_1") (pintype "passive"))
      (node (ref "C58") (pin "2") (pinfunction "2_2") (pintype "passive"))
      (node (ref "C65") (pin "2") (pinfunction "2_2") (pintype "passive"))
      (node (ref "C70") (pin "1") (pinfunction "1_1") (pintype "passive"))
      (node (ref "C72") (pin "2") (pinfunction "2_2") (pintype "passive"))
      (node (ref "C73") (pin "2") (pinfunction "2_2") (pintype "passive"))
      (node (ref "IC10") (pin "5") (pinfunction "VCC/VCCO_5") (pintype "power_in"))
      (node (ref "IC12") (pin "7") (pinfunction "V+_7") (pintype "power_in"))
      (node (ref "IC13") (pin "8") (pinfunction "VDD_8") (pintype "passive"))
      (node (ref "IC14") (pin "8") (pinfunction "VDD_8") (pintype "passive"))
      (node (ref "IC8") (pin "14") (pinfunction "VDD_14") (pintype "passive"))
      (node (ref "IC9") (pin "11") (pinfunction "VCC_11") (pintype "power_in"))
      (node (ref "IC9") (pin "12") (pinfunction "VCC_12") (pintype "power_in"))
      (node (ref "IC9") (pin "13") (pinfunction "VCC_13") (pintype "power_in"))
      (node (ref "IC9") (pin "24") (pinfunction "VCC_24") (pintype "power_in"))
      (node (ref "L5") (pin "2") (pinfunction "2_2") (pintype "passive"))
      (node (ref "R25") (pin "2") (pinfunction "2_2") (pintype "passive"))
      (node (ref "R39") (pin "2") (pinfunction "2_2") (pintype "passive"))
    )
    (net (code "3") (name "+3V3_OSC") (class "Default")
      (node (ref "C86") (pin "1") (pinfunction "1_1") (pintype "passive"))
      (node (ref "C98") (pin "1") (pinfunction "1_1") (pintype "passive"))
      (node (ref "IC15") (pin "1") (pinfunction "VDD_1") (pintype "power_in"))
      (node (ref "IC18") (pin "1") (pinfunction "VDD_1") (pintype "power_in"))
      (node (ref "L6") (pin "2") (pinfunction "2_2") (pintype "passive"))
      (node (ref "L7") (pin "2") (pinfunction "2_2") (pintype "passive"))
    )
    (net (code "4") (name "+5V") (class "Default")
      (node (ref "IC17") (pin "2") (pinfunction "IN_2") (pintype "power_in"))
    )
    (net (code "5") (name "/DAC_DMTD_DIN") (class "Default")
      (node (ref "IC18") (pin "7") (pinfunction "DIN_7") (pintype "input"))
    )
    (net (code "6") (name "/DAC_DMTD_SCLK") (class "Default")
      (node (ref "IC18") (pin "6") (pinfunction "SCLK_6") (pintype "input"))
    )
    (net (code "7") (name "/DAC_DMTD_SYNC") (class "Default")
      (node (ref "IC18") (pin "5") (pinfunction "/SYNC_5") (pintype "input"))
    )
    (net (code "8") (name "/DAC_REF_DIN") (class "Default")
      (node (ref "IC15") (pin "7") (pinfunction "DIN_7") (pintype "input"))
    )
    (net (code "9") (name "/DAC_REF_SCLK") (class "Default")
      (node (ref "IC15") (pin "6") (pinfunction "SCLK_6") (pintype "input"))
    )
    (net (code "10") (name "/DAC_REF_SYNC") (class "Default")
      (node (ref "IC15") (pin "5") (pinfunction "/SYNC_5") (pintype "input"))
    )
    (net (code "11") (name "/DMTDCLK+") (class "Default")
      (node (ref "IC11") (pin "11") (pinfunction "OUT1_11") (pintype "output"))
    )
    (net (code "12") (name "/DMTDCLK-") (class "Default")
      (node (ref "IC11") (pin "12") (pinfunction "/OUT1_12") (pintype "output"))
    )
    (net (code "13") (name "/DMTDCLK_MAIN+") (class "Default")
      (node (ref "IC11") (pin "7") (pinfunction "OUT0_7") (pintype "output"))
    )
    (net (code "14") (name "/DMTDCLK_MAIN-") (class "Default")
      (node (ref "IC11") (pin "8") (pinfunction "/OUT0_8") (pintype "output"))
    )
    (net (code "15") (name "/EXTPLL_LOCK") (class "Default")
      (node (ref "IC9") (pin "20") (pinfunction "~{LOCKED}_20") (pintype "output"))
    )
    (net (code "16") (name "/EXTPLL_OE") (class "Default")
      (node (ref "IC9") (pin "21") (pinfunction "OE_21") (pintype "input"))
    )
    (net (code "17") (name "/EXTPLL_SCLK") (class "Default")
      (node (ref "IC9") (pin "17") (pinfunction "SCLOCK_17") (pintype "input"))
    )
    (net (code "18") (name "/EXTPLL_SDATA") (class "Default")
      (node (ref "IC9") (pin "16") (pinfunction "SDATA_16") (pintype "input"))
    )
    (net (code "19") (name "/EXTPLL_SLOAD") (class "Default")
      (node (ref "IC9") (pin "15") (pinfunction "SLOAD_15") (pintype "input"))
    )
    (net (code "20") (name "/EXTPPSIN") (class "Default")
      (node (ref "IC8") (pin "2") (pinfunction "B_2") (pintype "input"))
      (node (ref "R30") (pin "2") (pinfunction "2_2") (pintype "passive"))
    )
    (net (code "21") (name "/EXTPPSOUT") (class "Default")
      (node (ref "R32") (pin "1") (pinfunction "1_1") (pintype "passive"))
    )
    (net (code "22") (name "/EXTREFIN_10M") (class "Default")
      (node (ref "C60") (pin "1") (pinfunction "1_1") (pintype "passive"))
      (node (ref "R33") (pin "2") (pinfunction "2_2") (pintype "passive"))
      (node (ref "R34") (pin "2") (pinfunction "2_2") (pintype "passive"))
    )
    (net (code "23") (name "/EXTREFIN_125M") (class "Default")
      (node (ref "C78") (pin "1") (pinfunction "1_1") (pintype "passive"))
      (node (ref "R41") (pin "2") (pinfunction "2_2") (pintype "passive"))
      (node (ref "R42") (pin "2") (pinfunction "2_2") (pintype "passive"))
    )
    (net (code "24") (name "/EXTREFOUT") (class "Default")
      (node (ref "R46") (pin "1") (pinfunction "1_1") (pintype "passive"))
    )
    (net (code "25") (name "/EXT_VBB") (class "Default")
      (node (ref "C74") (pin "1") (pinfunction "1_1") (pintype "passive"))
      (node (ref "IC12") (pin "3") (pinfunction "IN+_3") (pintype "input"))
      (node (ref "IC13") (pin "4") (pinfunction "VBB_4") (pintype "passive"))
    )
    (net (code "26") (name "/PPS_IN") (class "Default")
      (node (ref "IC8") (pin "5") (pinfunction "B_5") (pintype "input"))
    )
    (net (code "27") (name "/PPS_OUT") (class "Default")
      (node (ref "R26") (pin "2") (pinfunction "2_2") (pintype "passive"))
    )
    (net (code "28") (name "/REFCLK1_N") (class "Default")
      (node (ref "IC6") (pin "18") (pinfunction "/OUT8_18") (pintype "output"))
    )
    (net (code "29") (name "/REFCLK1_P") (class "Default")
      (node (ref "IC6") (pin "19") (pinfunction "OUT8_19") (pintype "output"))
    )
    (net (code "30") (name "/REFCLK2_N") (class "Default")
      (node (ref "IC6") (pin "39") (pinfunction "/OUT0_39") (pintype "output"))
    )
    (net (code "31") (name "/REFCLK2_P") (class "Default")
      (node (ref "IC6") (pin "40") (pinfunction "OUT0_40") (pintype "output"))
    )
    (net (code "32") (name "/REFCLK_EXT_FB+") (class "Default")
      (node (ref "IC7") (pin "7") (pinfunction "OUT0_7") (pintype "output"))
    )
    (net (code "33") (name "/REFCLK_EXT_FB-") (class "Default")
      (node (ref "IC7") (pin "8") (pinfunction "/OUT0_8") (pintype "output"))
    )
    (net (code "34") (name "/REFCLK_EXT_SEL") (class "Default")
      (node (ref "IC7") (pin "15") (pinfunction "SEL_15") (pintype "input"))
    )
    (net (code "35") (name "/REFCLK_FB_N") (class "Default")
      (node (ref "IC6") (pin "37") (pinfunction "/OUT1_37") (pintype "output"))
    )
    (net (code "36") (name "/REFCLK_FB_P") (class "Default")
      (node (ref "IC6") (pin "38") (pinfunction "OUT1_38") (pintype "output"))
    )
    (net (code "37") (name "/REFCLK_MAIN_N") (class "Default")
      (node (ref "IC6") (pin "16") (pinfunction "/OUT9_16") (pintype "output"))
    )
    (net (code "38") (name "/REFCLK_MAIN_P") (class "Default")
      (node (ref "IC6") (pin "17") (pinfunction "OUT9_17") (pintype "output"))
    )
    (net (code "39") (name "/REFCLK_UP0_N") (class "Default")
      (node (ref "IC6") (pin "24") (pinfunction "/OUT6_24") (pintype "output"))
    )
    (net (code "40") (name "/REFCLK_UP0_P") (class "Default")
      (node (ref "IC6") (pin "25") (pinfunction "OUT6_25") (pintype "output"))
    )
    (net (code "41") (name "/REFCLK_UP1_N") (class "Default")
      (node (ref "IC6") (pin "31") (pinfunction "/OUT3_31") (pintype "output"))
    )
    (net (code "42") (name "/REFCLK_UP1_P") (class "Default")
      (node (ref "IC6") (pin "32") (pinfunction "OUT3_32") (pintype "output"))
    )
    (net (code "43") (name "/REFCLK_VCSO_SEL") (class "Default")
      (node (ref "IC6") (pin "42") (pinfunction "SEL_42") (pintype "input"))
    )
    (net (code "44") (name "GND") (class "Default")
      (node (ref "C100") (pin "1") (pinfunction "1_1") (pintype "passive"))
      (node (ref "C101") (pin "1") (pinfunction "1_1") (pintype "passive"))
      (node (ref "C41") (pin "2") (pinfunction "2_2") (pintype "passive"))
      (node (ref "C42") (pin "2") (pinfunction "2_2") (pintype "passive"))
      (node (ref "C43") (pin "2") (pinfunction "2_2") (pintype "passive"))
      (node (ref "C44") (pin "2") (pinfunction "2_2") (pintype "passive"))
      (node (ref "C45") (pin "1") (pinfunction "1_1") (pintype "passive"))
      (node (ref "C46") (pin "2") (pinfunction "2_2") (pintype "passive"))
      (node (ref "C47") (pin "2") (pinfunction "2_2") (pintype "passive"))
      (node (ref "C48") (pin "1") (pinfunction "1_1") (pintype "passive"))
      (node (ref "C49") (pin "1") (pinfunction "1_1") (pintype "passive"))
      (node (ref "C50") (pin "1") (pinfunction "1_1") (pintype "passive"))
      (node (ref "C51") (pin "2") (pinfunction "2_2") (pintype "passive"))
      (node (ref "C52") (pin "1") (pinfunction "1_1") (pintype "passive"))
      (node (ref "C53") (pin "2") (pinfunction "2_2") (pintype "passive"))
      (node (ref "C54") (pin "1") (pinfunction "1_1") (pintype "passive"))
      (node (ref "C55") (pin "1") (pinfunction "1_1") (pintype "passive"))
      (node (ref "C56") (pin "1") (pinfunction "1_1") (pintype "passive"))
      (node (ref "C58") (pin "1") (pinfunction "1_1") (pintype "passive"))
      (node (ref "C59") (pin "2") (pinfunction "2_2") (pintype "passive"))
      (node (ref "C62") (pin "2") (pinfunction "2_2") (pintype "passive"))
      (node (ref "C64") (pin "1") (pinfunction "1_1") (pintype "passive"))
      (node (ref "C65") (pin "1") (pinfunction "1_1") (pintype "passive"))
      (node (ref "C66") (pin "2") (pinfunction "2_2") (pintype "passive"))
      (node (ref "C67") (pin "1") (pinfunction "1_1") (pintype "passive"))
      (node (ref "C68") (pin "2") (pinfunction "2_2") (pintype "passive"))
      (node (ref "C69") (pin "1") (pinfunction "1_1") (pintype "passive"))
      (node (ref "C70") (pin "2") (pinfunction "2_2") (pintype "passive"))
      (node (ref "C72") (pin "1") (pinfunction "1_1") (pintype "passive"))
      (node (ref "C73") (pin "1") (pinfunction "1_1") (pintype "passive"))
      (node (ref "C74") (pin "2") (pinfunction "2_2") (pintype "passive"))
      (node (ref "C75") (pin "1") (pinfunction "1_1") (pintype "passive"))
      (node (ref "C76") (pin "2") (pinfunction "2_2") (pintype "passive"))
      (node (ref "C81") (pin "2") (pinfunction "2_2") (pintype "passive"))
      (node (ref "C82") (pin "2") (pinfunction "2_2") (pintype "passive"))
      (node (ref "C84") (pin "2") (pinfunction "2_2") (pintype "passive"))
      (node (ref "C85") (pin "1") (pinfunction "1_1") (pintype "passive"))
      (node (ref "C86") (pin "2") (pinfunction "2_2") (pintype "passive"))
      (node (ref "C87") (pin "1") (pinfunction "1_1") (pintype "passive"))
      (node (ref "C90") (pin "1") (pinfunction "1_1") (pintype "passive"))
      (node (ref "C91") (pin "1") (pinfunction "1_1") (pintype "passive"))
      (node (ref "C93") (pin "1") (pinfunction "1_1") (pintype "passive"))
      (node (ref "C94") (pin "1") (pinfunction "1_1") (pintype "passive"))
      (node (ref "C96") (pin "1") (pinfunction "1_1") (pintype "passive"))
      (node (ref "C98") (pin "2") (pinfunction "2_2") (pintype "passive"))
      (node (ref "C99") (pin "1") (pinfunction "1_1") (pintype "passive"))
      (node (ref "IC10") (pin "2") (pinfunction "VEE_2") (pintype "power_in"))
      (node (ref "IC11") (pin "14") (pinfunction "GND_14") (pintype "power_in"))
      (node (ref "IC11") (pin "15") (pinfunction "SEL_15") (pintype "input"))
      (node (ref "IC11") (pin "17") (pinfunction "GND_17") (pintype "power_in"))
      (node (ref "IC11") (pin "18") (pinfunction "GND_18") (pintype "power_in"))
      (node (ref "IC11") (pin "PAD") (pinfunction "GND_PAD_PAD") (pintype "power_in"))
      (node (ref "IC12") (pin "4") (pinfunction "V-_4") (pintype "power_in"))
      (node (ref "IC13") (pin "5") (pinfunction "VEE_5") (pintype "passive"))
      (node (ref "IC14") (pin "5") (pinfunction "GND_5") (pintype "passive"))
      (node (ref "IC15") (pin "8") (pinfunction "GND_8") (pintype "power_in"))
      (node (ref "IC16") (pin "2") (pinfunction "OSelect_2") (pintype "input"))
      (node (ref "IC16") (pin "3") (pinfunction "GND_3") (pintype "power_in"))
      (node (ref "IC17") (pin "4") (pinfunction "GND_4") (pintype "power_in"))
      (node (ref "IC17") (pin "8") (pinfunction "SEL_8") (pintype "input"))
      (node (ref "IC18") (pin "8") (pinfunction "GND_8") (pintype "power_in"))
      (node (ref "IC19") (pin "2") (pinfunction "OSelect_2") (pintype "input"))
      (node (ref "IC19") (pin "3") (pinfunction "GND_3") (pintype "power_in"))
      (node (ref "IC6") (pin "1") (pinfunction "GND_1") (pintype "power_in"))
      (node (ref "IC6") (pin "11") (pinfunction "GND_11") (pintype "power_in"))
      (node (ref "IC6") (pin "6") (pinfunction "GND_6") (pintype "power_in"))
      (node (ref "IC6") (pin "PAD") (pinfunction "GND_PAD_PAD") (pintype "power_in"))
      (node (ref "IC7") (pin "14") (pinfunction "GND_14") (pintype "power_in"))
      (node (ref "IC7") (pin "17") (pinfunction "GND_17") (pintype "power_in"))
      (node (ref "IC7") (pin "18") (pinfunction "GND_18") (pintype "power_in"))
      (node (ref "IC7") (pin "PAD") (pinfunction "GND_PAD_PAD") (pintype "power_in"))
      (node (ref "IC8") (pin "1") (pinfunction "~{A}_1") (pintype "input"))
      (node (ref "IC8") (pin "4") (pinfunction "~{A}_4") (pintype "input"))
      (node (ref "IC8") (pin "7") (pinfunction "GND_7") (pintype "passive"))
      (node (ref "IC9") (pin "1") (pinfunction "GND_1") (pintype "power_in"))
      (node (ref "IC9") (pin "18") (pinfunction "GND_18") (pintype "power_in"))
      (node (ref "IC9") (pin "19") (pinfunction "GND_19") (pintype "power_in"))
      (node (ref "IC9") (pin "6") (pinfunction "GND_6") (pintype "power_in"))
      (node (ref "IC9") (pin "9") (pinfunction "GND_9") (pintype "power_in"))
      (node (ref "IC9") (pin "PAD") (pinfunction "GND_PAD_PAD") (pintype "power_in"))
      (node (ref "R27") (pin "1") (pinfunction "1_1") (pintype "passive"))
      (node (ref "R30") (pin "1") (pinfunction "1_1") (pintype "passive"))
      (node (ref "R35") (pin "1") (pinfunction "1_1") (pintype "passive"))
      (node (ref "R36") (pin "1") (pinfunction "1_1") (pintype "passive"))
      (node (ref "R43") (pin "1") (pinfunction "1_1") (pintype "passive"))
      (node (ref "R44") (pin "1") (pinfunction "1_1") (pintype "passive"))
      (node (ref "R48") (pin "1") (pinfunction "1_1") (pintype "passive"))
      (node (ref "R49") (pin "1") (pinfunction "1_1") (pintype "passive"))
      (node (ref "R50") (pin "1") (pinfunction "1_1") (pintype "passive"))
      (node (ref "R51") (pin "1") (pinfunction "1_1") (pintype "passive"))
    )
    (net (code "45") (name "Net-(C55-Pad2)") (class "Default")
      (node (ref "C55") (pin "2") (pinfunction "2_2") (pintype "passive"))
      (node (ref "C56") (pin "2") (pinfunction "2_2") (pintype "passive"))
      (node (ref "R25") (pin "1") (pinfunction "1_1") (pintype "passive"))
      (node (ref "R27") (pin "2") (pinfunction "2_2") (pintype "passive"))
      (node (ref "R28") (pin "2") (pinfunction "2_2") (pintype "passive"))
      (node (ref "R29") (pin "2") (pinfunction "2_2") (pintype "passive"))
    )
    (net (code "46") (name "Net-(C60-Pad2)") (class "Default")
      (node (ref "C60") (pin "2") (pinfunction "2_2") (pintype "passive"))
      (node (ref "R31") (pin "1") (pinfunction "1_1") (pintype "passive"))
    )
    (net (code "47") (name "Net-(C62-Pad1)") (class "Default")
      (node (ref "C62") (pin "1") (pinfunction "1_1") (pintype "passive"))
      (node (ref "R33") (pin "1") (pinfunction "1_1") (pintype "passive"))
      (node (ref "R34") (pin "1") (pinfunction "1_1") (pintype "passive"))
    )
    (net (code "48") (name "Net-(C78-Pad2)") (class "Default")
      (node (ref "C78") (pin "2") (pinfunction "2_2") (pintype "passive"))
      (node (ref "R40") (pin "1") (pinfunction "1_1") (pintype "passive"))
    )
    (net (code "49") (name "Net-(C82-Pad1)") (class "Default")
      (node (ref "C82") (pin "1") (pinfunction "1_1") (pintype "passive"))
      (node (ref "R41") (pin "1") (pinfunction "1_1") (pintype "passive"))
      (node (ref "R42") (pin "1") (pinfunction "1_1") (pintype "passive"))
    )
    (net (code "50") (name "Net-(D3-A)") (class "Default")
      (node (ref "C64") (pin "2") (pinfunction "2_2") (pintype "passive"))
      (node (ref "D3") (pin "1") (pinfunction "A_1") (pintype "passive"))
      (node (ref "D3") (pin "2") (pinfunction "K_2") (pintype "passive"))
    )
    (net (code "51") (name "Net-(D3-C)") (class "Default")
      (node (ref "D3") (pin "3") (pinfunction "C_3") (pintype "passive"))
      (node (ref "IC10") (pin "3") (pinfunction "VP_3") (pintype "input"))
      (node (ref "R28") (pin "1") (pinfunction "1_1") (pintype "passive"))
      (node (ref "R31") (pin "2") (pinfunction "2_2") (pintype "passive"))
    )
    (net (code "52") (name "Net-(D4-A)") (class "Default")
      (node (ref "C84") (pin "1") (pinfunction "1_1") (pintype "passive"))
      (node (ref "D4") (pin "1") (pinfunction "A_1") (pintype "passive"))
      (node (ref "D4") (pin "2") (pinfunction "K_2") (pintype "passive"))
    )
    (net (code "53") (name "Net-(D4-C)") (class "Default")
      (node (ref "D4") (pin "3") (pinfunction "C_3") (pintype "passive"))
      (node (ref "IC13") (pin "2") (pinfunction "D_2") (pintype "input"))
      (node (ref "R38") (pin "1") (pinfunction "1_1") (pintype "passive"))
      (node (ref "R40") (pin "2") (pinfunction "2_2") (pintype "passive"))
    )
    (net (code "54") (name "Net-(IC6A-IN0)") (class "Default")
      (node (ref "IC6") (pin "2") (pinfunction "IN0_2") (pintype "input"))
      (node (ref "IC7") (pin "11") (pinfunction "OUT1_11") (pintype "output"))
    )
    (net (code "55") (name "Net-(IC6A-IN1)") (class "Default")
      (node (ref "C88") (pin "2") (pinfunction "2_2") (pintype "passive"))
      (node (ref "IC6") (pin "7") (pinfunction "IN1_7") (pintype "input"))
    )
    (net (code "56") (name "Net-(IC6A-VREF_AC1)") (class "Default")
      (node (ref "C92") (pin "2") (pinfunction "2_2") (pintype "passive"))
      (node (ref "IC6") (pin "8") (pinfunction "VT1_8") (pintype "passive"))
      (node (ref "IC6") (pin "9") (pinfunction "VREF_AC1_9") (pintype "input"))
    )
    (net (code "57") (name "Net-(IC6A-{slash}IN0)") (class "Default")
      (node (ref "IC6") (pin "5") (pinfunction "/IN0_5") (pintype "input"))
      (node (ref "IC7") (pin "12") (pinfunction "/OUT1_12") (pintype "output"))
    )
    (net (code "58") (name "Net-(IC6A-{slash}IN1)") (class "Default")
      (node (ref "C89") (pin "2") (pinfunction "2_2") (pintype "passive"))
      (node (ref "IC6") (pin "10") (pinfunction "/IN1_10") (pintype "input"))
    )
    (net (code "59") (name "Net-(IC7A-IN0)") (class "Default")
      (node (ref "C77") (pin "2") (pinfunction "2_2") (pintype "passive"))
      (node (ref "IC7") (pin "5") (pinfunction "IN0_5") (pintype "input"))
    )
    (net (code "60") (name "Net-(IC7A-IN1)") (class "Default")
      (node (ref "C61") (pin "2") (pinfunction "2_2") (pintype "passive"))
      (node (ref "IC7") (pin "23") (pinfunction "IN1_23") (pintype "input"))
    )
    (net (code "61") (name "Net-(IC7A-VREF_AC0)") (class "Default")
      (node (ref "C80") (pin "2") (pinfunction "2_2") (pintype "passive"))
      (node (ref "IC7") (pin "3") (pinfunction "VREF_AC0_3") (pintype "input"))
      (node (ref "IC7") (pin "4") (pinfunction "VT0_4") (pintype "passive"))
    )
    (net (code "62") (name "Net-(IC7A-VREF_AC1)") (class "Default")
      (node (ref "C83") (pin "2") (pinfunction "2_2") (pintype "passive"))
      (node (ref "IC7") (pin "21") (pinfunction "VREF_AC1_21") (pintype "input"))
      (node (ref "IC7") (pin "22") (pinfunction "VT1_22") (pintype "passive"))
    )
    (net (code "63") (name "Net-(IC7A-{slash}IN0)") (class "Default")
      (node (ref "C79") (pin "2") (pinfunction "2_2") (pintype "passive"))
      (node (ref "IC7") (pin "2") (pinfunction "/IN0_2") (pintype "input"))
    )
    (net (code "64") (name "Net-(IC7A-{slash}IN1)") (class "Default")
      (node (ref "C63") (pin "2") (pinfunction "2_2") (pintype "passive"))
      (node (ref "IC7") (pin "20") (pinfunction "/IN1_20") (pintype "input"))
    )
    (net (code "65") (name "Net-(IC8A-Y)") (class "Default")
      (node (ref "IC8") (pin "3") (pinfunction "Y_3") (pintype "tri_state"))
      (node (ref "R26") (pin "1") (pinfunction "1_1") (pintype "passive"))
    )
    (net (code "66") (name "Net-(IC8B-Y)") (class "Default")
      (node (ref "IC8") (pin "6") (pinfunction "Y_6") (pintype "tri_state"))
      (node (ref "R32") (pin "2") (pinfunction "2_2") (pintype "passive"))
    )
    (net (code "67") (name "Net-(IC9A-CLKOUT)") (class "Default")
      (node (ref "C61") (pin "1") (pinfunction "1_1") (pintype "passive"))
      (node (ref "IC9") (pin "22") (pinfunction "CLKOUT_22") (pintype "output"))
      (node (ref "R35") (pin "2") (pinfunction "2_2") (pintype "passive"))
    )
    (net (code "68") (name "Net-(IC9A-~{CLKOUT})") (class "Default")
      (node (ref "C63") (pin "1") (pinfunction "1_1") (pintype "passive"))
      (node (ref "IC9") (pin "23") (pinfunction "~{CLKOUT}_23") (pintype "output"))
      (node (ref "R36") (pin "2") (pinfunction "2_2") (pintype "passive"))
    )
    (net (code "69") (name "Net-(IC9B-VCC_PLL)") (class "Default")
      (node (ref "C49") (pin "2") (pinfunction "2_2") (pintype "passive"))
      (node (ref "C50") (pin "2") (pinfunction "2_2") (pintype "passive"))
      (node (ref "IC9") (pin "3") (pinfunction "VCC_PLL_3") (pintype "power_in"))
      (node (ref "L5") (pin "1") (pinfunction "1_1") (pintype "passive"))
    )
    (net (code "70") (name "Net-(IC10-Q)") (class "Default")
      (node (ref "IC10") (pin "1") (pinfunction "Q_1") (pintype "open_collector"))
      (node (ref "IC9") (pin "8") (pinfunction "X1/CLK_8") (pintype "passive"))
    )
    (net (code "71") (name "Net-(IC10-VN)") (class "Default")
      (node (ref "IC10") (pin "4") (pinfunction "VN_4") (pintype "input"))
      (node (ref "R29") (pin "1") (pinfunction "1_1") (pintype "passive"))
    )
    (net (code "72") (name "Net-(IC11A-IN0)") (class "Default")
      (node (ref "C95") (pin "2") (pinfunction "2_2") (pintype "passive"))
      (node (ref "IC11") (pin "5") (pinfunction "IN0_5") (pintype "input"))
    )
    (net (code "73") (name "Net-(IC11A-VREF_AC0)") (class "Default")
      (node (ref "C102") (pin "2") (pinfunction "2_2") (pintype "passive"))
      (node (ref "IC11") (pin "3") (pinfunction "VREF_AC0_3") (pintype "input"))
      (node (ref "IC11") (pin "4") (pinfunction "VT0_4") (pintype "passive"))
    )
    (net (code "74") (name "Net-(IC11A-{slash}IN0)") (class "Default")
      (node (ref "C97") (pin "2") (pinfunction "2_2") (pintype "passive"))
      (node (ref "IC11") (pin "2") (pinfunction "/IN0_2") (pintype "input"))
    )
    (net (code "75") (name "Net-(IC12-IN-)") (class "Default")
      (node (ref "C75") (pin "2") (pinfunction "2_2") (pintype "passive"))
      (node (ref "C76") (pin "1") (pinfunction "1_1") (pintype "passive"))
      (node (ref "IC12") (pin "1") (pinfunction "OUT_1") (pintype "output"))
      (node (ref "IC12") (pin "2") (pinfunction "IN-_2") (pintype "input"))
      (node (ref "R37") (pin "2") (pinfunction "2_2") (pintype "passive"))
      (node (ref "R38") (pin "2") (pinfunction "2_2") (pintype "passive"))
    )
    (net (code "76") (name "Net-(IC13A-Q)") (class "Default")
      (node (ref "C77") (pin "1") (pinfunction "1_1") (pintype "passive"))
      (node (ref "IC13") (pin "7") (pinfunction "Q_7") (pintype "output"))
      (node (ref "R43") (pin "2") (pinfunction "2_2") (pintype "passive"))
    )
    (net (code "77") (name "Net-(IC13A-{slash}D)") (class "Default")
      (node (ref "C81") (pin "1") (pinfunction "1_1") (pintype "passive"))
      (node (ref "IC13") (pin "3") (pinfunction "/D_3") (pintype "input"))
      (node (ref "R37") (pin "1") (pinfunction "1_1") (pintype "passive"))
      (node (ref "R39") (pin "1") (pinfunction "1_1") (pintype "passive"))
    )
    (net (code "78") (name "Net-(IC13A-{slash}Q)") (class "Default")
      (node (ref "C79") (pin "1") (pinfunction "1_1") (pintype "passive"))
      (node (ref "IC13") (pin "6") (pinfunction "/Q_6") (pintype "output"))
      (node (ref "R44") (pin "2") (pinfunction "2_2") (pintype "passive"))
    )
    (net (code "79") (name "Net-(IC14A-D)") (class "Default")
      (node (ref "IC14") (pin "2") (pinfunction "D_2") (pintype "input"))
      (node (ref "IC6") (pin "21") (pinfunction "OUT7_21") (pintype "output"))
      (node (ref "R47") (pin "1") (pinfunction "1_1") (pintype "passive"))
    )
    (net (code "80") (name "Net-(IC14A-Q)") (class "Default")
      (node (ref "IC14") (pin "7") (pinfunction "Q_7") (pintype "output"))
      (node (ref "R46") (pin "2") (pinfunction "2_2") (pintype "passive"))
    )
    (net (code "81") (name "Net-(IC14A-{slash}D)") (class "Default")
      (node (ref "IC14") (pin "3") (pinfunction "/D_3") (pintype "input"))
      (node (ref "IC6") (pin "20") (pinfunction "/OUT7_20") (pintype "output"))
      (node (ref "R47") (pin "2") (pinfunction "2_2") (pintype "passive"))
    )
    (net (code "82") (name "Net-(IC15-VFB)") (class "Default")
      (node (ref "IC15") (pin "3") (pinfunction "VFB_3") (pintype "input"))
      (node (ref "IC15") (pin "4") (pinfunction "VOUT_4") (pintype "output"))
      (node (ref "R45") (pin "1") (pinfunction "1_1") (pintype "passive"))
    )
    (net (code "83") (name "Net-(IC15-VREF)") (class "Default")
      (node (ref "C93") (pin "2") (pinfunction "2_2") (pintype "passive"))
      (node (ref "C94") (pin "2") (pinfunction "2_2") (pintype "passive"))
      (node (ref "IC15") (pin "2") (pinfunction "VREF_2") (pintype "input"))
      (node (ref "IC17") (pin "6") (pinfunction "OUT_6") (pintype "power_in"))
      (node (ref "IC18") (pin "2") (pinfunction "VREF_2") (pintype "input"))
    )
    (net (code "84") (name "Net-(IC16-COutput)") (class "Default")
      (node (ref "C89") (pin "1") (pinfunction "1_1") (pintype "passive"))
      (node (ref "IC16") (pin "5") (pinfunction "COutput_5") (pintype "output"))
      (node (ref "R49") (pin "2") (pinfunction "2_2") (pintype "passive"))
    )
    (net (code "85") (name "Net-(IC16-Output)") (class "Default")
      (node (ref "C88") (pin "1") (pinfunction "1_1") (pintype "passive"))
      (node (ref "IC16") (pin "4") (pinfunction "Output_4") (pintype "output"))
      (node (ref "R48") (pin "2") (pinfunction "2_2") (pintype "passive"))
    )
    (net (code "86") (name "Net-(IC16-VC)") (class "Default")
      (node (ref "C90") (pin "2") (pinfunction "2_2") (pintype "passive"))
      (node (ref "C91") (pin "2") (pinfunction "2_2") (pintype "passive"))
      (node (ref "IC16") (pin "1") (pinfunction "VC_1") (pintype "input"))
      (node (ref "R45") (pin "2") (pinfunction "2_2") (pintype "passive"))
    )
    (net (code "87") (name "Net-(IC16-VCC)") (class "Default")
      (node (ref "C85") (pin "2") (pinfunction "2_2") (pintype "passive"))
      (node (ref "C87") (pin "2") (pinfunction "2_2") (pintype "passive"))
      (node (ref "IC16") (pin "6") (pinfunction "VCC_6") (pintype "power_in"))
      (node (ref "L6") (pin "1") (pinfunction "1_1") (pintype "passive"))
    )
    (net (code "88") (name "Net-(IC18-VFB)") (class "Default")
      (node (ref "IC18") (pin "3") (pinfunction "VFB_3") (pintype "input"))
      (node (ref "IC18") (pin "4") (pinfunction "VOUT_4") (pintype "output"))
      (node (ref "R52") (pin "1") (pinfunction "1_1") (pintype "passive"))
    )
    (net (code "89") (name "Net-(IC19-COutput)") (class "Default")
      (node (ref "C97") (pin "1") (pinfunction "1_1") (pintype "passive"))
      (node (ref "IC19") (pin "5") (pinfunction "COutput_5") (pintype "output"))
      (node (ref "R51") (pin "2") (pinfunction "2_2") (pintype "passive"))
    )
    (net (code "90") (name "Net-(IC19-Output)") (class "Default")
      (node (ref "C95") (pin "1") (pinfunction "1_1") (pintype "passive"))
      (node (ref "IC19") (pin "4") (pinfunction "Output_4") (pintype "output"))
      (node (ref "R50") (pin "2") (pinfunction "2_2") (pintype "passive"))
    )
    (net (code "91") (name "Net-(IC19-VC)") (class "Default")
      (node (ref "C100") (pin "2") (pinfunction "2_2") (pintype "passive"))
      (node (ref "C101") (pin "2") (pinfunction "2_2") (pintype "passive"))
      (node (ref "IC19") (pin "1") (pinfunction "VC_1") (pintype "input"))
      (node (ref "R52") (pin "2") (pinfunction "2_2") (pintype "passive"))
    )
    (net (code "92") (name "Net-(IC19-VCC)") (class "Default")
      (node (ref "C96") (pin "2") (pinfunction "2_2") (pintype "passive"))
      (node (ref "C99") (pin "2") (pinfunction "2_2") (pintype "passive"))
      (node (ref "IC19") (pin "6") (pinfunction "VCC_6") (pintype "power_in"))
      (node (ref "L7") (pin "1") (pinfunction "1_1") (pintype "passive"))
    )
    (net (code "93") (name "unconnected-(IC6A-OUT2-Pad36)") (class "Default")
      (node (ref "IC6") (pin "36") (pinfunction "OUT2_36") (pintype "output"))
    )
    (net (code "94") (name "unconnected-(IC6A-OUT4-Pad30)") (class "Default")
      (node (ref "IC6") (pin "30") (pinfunction "OUT4_30") (pintype "output"))
    )
    (net (code "95") (name "unconnected-(IC6A-OUT5-Pad27)") (class "Default")
      (node (ref "IC6") (pin "27") (pinfunction "OUT5_27") (pintype "output"))
    )
    (net (code "96") (name "unconnected-(IC6A-VREF_AC0-Pad4)") (class "Default")
      (node (ref "IC6") (pin "4") (pinfunction "VREF_AC0_4") (pintype "input+no_connect"))
    )
    (net (code "97") (name "unconnected-(IC6A-VT0-Pad3)") (class "Default")
      (node (ref "IC6") (pin "3") (pinfunction "VT0_3") (pintype "passive+no_connect"))
    )
    (net (code "98") (name "unconnected-(IC6A-{slash}OUT2-Pad35)") (class "Default")
      (node (ref "IC6") (pin "35") (pinfunction "/OUT2_35") (pintype "output"))
    )
    (net (code "99") (name "unconnected-(IC6A-{slash}OUT4-Pad29)") (class "Default")
      (node (ref "IC6") (pin "29") (pinfunction "/OUT4_29") (pintype "output"))
    )
    (net (code "100") (name "unconnected-(IC6A-{slash}OUT5-Pad26)") (class "Default")
      (node (ref "IC6") (pin "26") (pinfunction "/OUT5_26") (pintype "output"))
    )
    (net (code "101") (name "unconnected-(IC9A-X2-Pad7)") (class "Default")
      (node (ref "IC9") (pin "7") (pinfunction "X2_7") (pintype "passive"))
    )
    (net (code "102") (name "unconnected-(IC11A-IN1-Pad23)") (class "Default")
      (node (ref "IC11") (pin "23") (pinfunction "IN1_23") (pintype "input+no_connect"))
    )
    (net (code "103") (name "unconnected-(IC11A-VREF_AC1-Pad21)") (class "Default")
      (node (ref "IC11") (pin "21") (pinfunction "VREF_AC1_21") (pintype "input+no_connect"))
    )
    (net (code "104") (name "unconnected-(IC11A-VT1-Pad22)") (class "Default")
      (node (ref "IC11") (pin "22") (pinfunction "VT1_22") (pintype "passive+no_connect"))
    )
    (net (code "105") (name "unconnected-(IC11A-{slash}IN1-Pad20)") (class "Default")
      (node (ref "IC11") (pin "20") (pinfunction "/IN1_20") (pintype "input+no_connect"))
    )
    (net (code "106") (name "unconnected-(IC14A-VBB-Pad4)") (class "Default")
      (node (ref "IC14") (pin "4") (pinfunction "VBB_4") (pintype "passive"))
    )
    (net (code "107") (name "unconnected-(IC17-NC-Pad1)") (class "Default")
      (node (ref "IC17") (pin "1") (pinfunction "NC_1") (pintype "passive"))
    )
    (net (code "108") (name "unconnected-(IC17-NC-Pad7)") (class "Default")
      (node (ref "IC17") (pin "7") (pinfunction "NC_7") (pintype "passive"))
    )
    (net (code "109") (name "unconnected-(IC17-TEMP-Pad3)") (class "Default")
      (node (ref "IC17") (pin "3") (pinfunction "TEMP_3") (pintype "passive"))
    )
    (net (code "110") (name "unconnected-(IC17-TRIM-Pad5)") (class "Default")
      (node (ref "IC17") (pin "5") (pinfunction "TRIM_5") (pintype "passive"))
    )
  )
)
